# Servos.net
KiCad netlist of a schematic drawn in Altium Designer
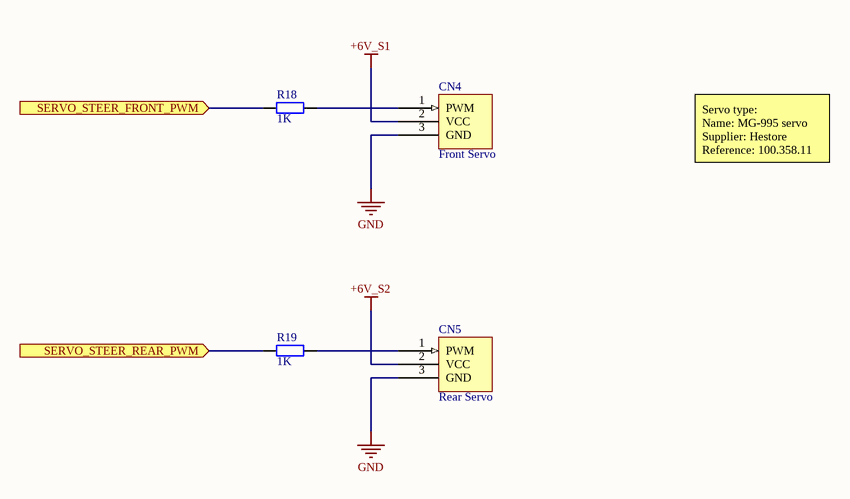
[diagram p0: Servos.SchDoc]

(export (version "E")
  (design (tool "Eeschema 10.0.6"))
  (components
    (comp (ref "CN4")
      (value "Front Servo")
      (footprint "FP_CONN3_TUSKE_254MM")
      (description "Steering servo\r\nMG-995 servo")
      (libsource (lib "LKBulls2023") (part "Connector_servo"))
    )
    (comp (ref "CN5")
      (value "Rear Servo")
      (footprint "FP_CONN3_TUSKE_254MM")
      (description "Steering servo\r\nMG-995 servo")
      (libsource (lib "LKBulls2023") (part "Connector_servo"))
    )
    (comp (ref "R18")
      (value "1K")
      (footprint "FP_0805_RES")
      (description "Resistor")
      (fields (field (name "TOLERANCE") "5%") (field (name "POWER") "0.125W"))
      (libsource (lib "LKBulls2023") (part "RES"))
    )
    (comp (ref "R19")
      (value "1K")
      (footprint "FP_0805_RES")
      (description "Resistor")
      (fields (field (name "TOLERANCE") "5%") (field (name "POWER") "0.125W"))
      (libsource (lib "LKBulls2023") (part "RES"))
    )
  )
  (nets
    (net (code "1") (name "+6V_S1") (class "Default")
      (node (ref "CN4") (pin "2") (pinfunction "VCC_2") (pintype "power_in"))
    )
    (net (code "2") (name "+6V_S2") (class "Default")
      (node (ref "CN5") (pin "2") (pinfunction "VCC_2") (pintype "power_in"))
    )
    (net (code "3") (name "/SERVO_STEER_FRONT_PWM") (class "Default")
      (node (ref "R18") (pin "1") (pinfunction "1_1") (pintype "passive"))
    )
    (net (code "4") (name "/SERVO_STEER_REAR_PWM") (class "Default")
      (node (ref "R19") (pin "1") (pinfunction "1_1") (pintype "passive"))
    )
    (net (code "5") (name "GND") (class "Default")
      (node (ref "CN4") (pin "3") (pinfunction "GND_3") (pintype "passive"))
      (node (ref "CN5") (pin "3") (pinfunction "GND_3") (pintype "passive"))
    )
    (net (code "6") (name "Net-(CN4-PWM)") (class "Default")
      (node (ref "CN4") (pin "1") (pinfunction "PWM_1") (pintype "input"))
      (node (ref "R18") (pin "2") (pinfunction "2_2") (pintype "passive"))
    )
    (net (code "7") (name "Net-(CN5-PWM)") (class "Default")
      (node (ref "CN5") (pin "1") (pinfunction "PWM_1") (pintype "input"))
      (node (ref "R19") (pin "2") (pinfunction "2_2") (pintype "passive"))
    )
  )
)
